# TOP.net
KiCad netlist of a schematic drawn in Altium Designer
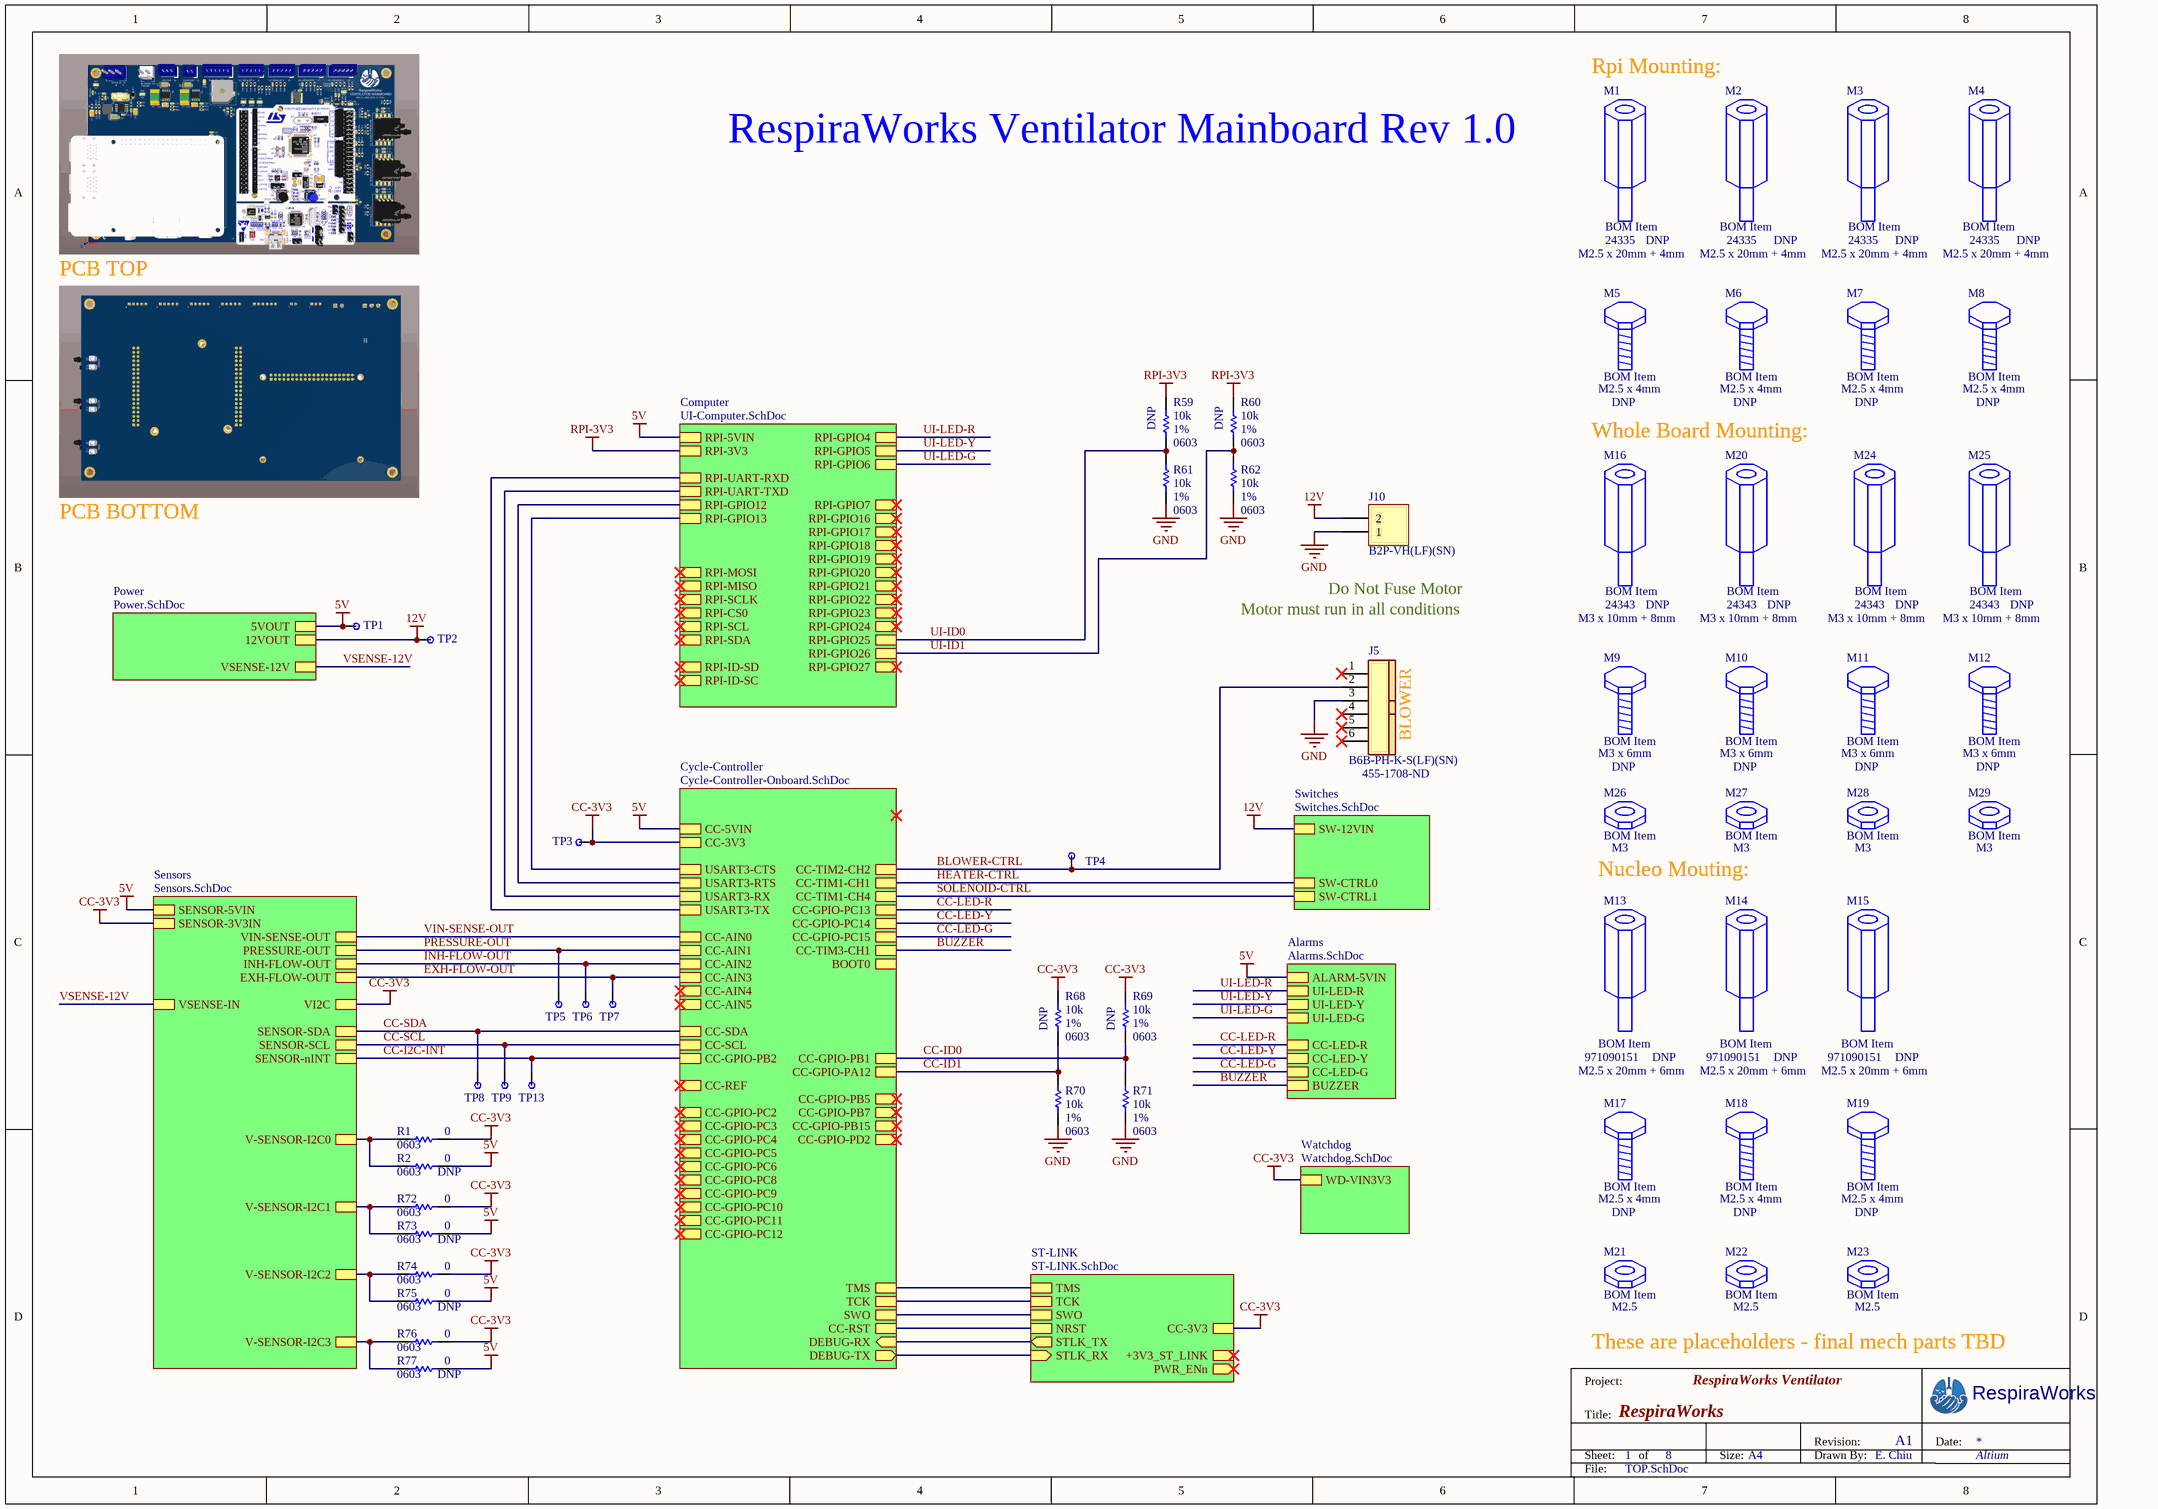
[diagram p0: TOP.SchDoc]

(export (version "E")
  (design (tool "Eeschema 10.0.6"))
  (components
    (comp (ref "J5")
      (value "B6B-PH-K-S(LF)(SN)")
      (footprint "JST_B6B-XH-AM")
      (description "CONN HEADER PH TOP 6POS 2MM")
      (fields
        (field (name "MANUFACTURER") "JST Sales America Inc.")
        (field (name "SUPPLIER PART NUMBER 1") "455-1708-ND")
      )
      (libsource (lib "JST XH") (part "B6B-PH-K-S(LF)(SN)"))
    )
    (comp (ref "J10")
      (value "B2P-VH(LF)(SN)")
      (footprint "B2P-VH(LF)(SN)")
      (description "JST-VH HEADER VERT 2POS 3.96MM")
      (fields (field (name "MANUFACTURER") "JST") (field (name "MANUFACTURER P/N") "B2P-VH(LF)(SN)"))
      (libsource (lib "JST") (part "B2P-VH(LF)(SN)"))
    )
    (comp (ref "M1")
      (value "BOM Item")
      (description "[BOM Item] Generic Standoff")
      (fields
        (field (name "MANUFACTURER") "Keystone")
        (field (name "MANUFACTURER P/N") "24335")
        (field (name "DO NOT POPULATE") "DNP")
        (field (name "ALTIUM_VALUE") "M2.5 x 20mm + 4mm")
      )
      (libsource (lib "generic") (part "STANDOFF"))
    )
    (comp (ref "M2")
      (value "BOM Item")
      (description "[BOM Item] Generic Standoff")
      (fields
        (field (name "MANUFACTURER") "Keystone")
        (field (name "MANUFACTURER P/N") "24335")
        (field (name "DO NOT POPULATE") "DNP")
        (field (name "ALTIUM_VALUE") "M2.5 x 20mm + 4mm")
      )
      (libsource (lib "generic") (part "STANDOFF"))
    )
    (comp (ref "M3")
      (value "BOM Item")
      (description "[BOM Item] Generic Standoff")
      (fields
        (field (name "MANUFACTURER") "Keystone")
        (field (name "MANUFACTURER P/N") "24335")
        (field (name "DO NOT POPULATE") "DNP")
        (field (name "ALTIUM_VALUE") "M2.5 x 20mm + 4mm")
      )
      (libsource (lib "generic") (part "STANDOFF"))
    )
    (comp (ref "M4")
      (value "BOM Item")
      (description "[BOM Item] Generic Standoff")
      (fields
        (field (name "MANUFACTURER") "Keystone")
        (field (name "MANUFACTURER P/N") "24335")
        (field (name "DO NOT POPULATE") "DNP")
        (field (name "ALTIUM_VALUE") "M2.5 x 20mm + 4mm")
      )
      (libsource (lib "generic") (part "STANDOFF"))
    )
    (comp (ref "M5")
      (value "BOM Item")
      (description "[BOM Item] Generic Nut")
      (fields
        (field (name "MANUFACTURER") "Keystone")
        (field (name "DO NOT POPULATE") "DNP")
        (field (name "ALTIUM_VALUE") "M2.5 x 4mm")
      )
      (libsource (lib "generic") (part "SCREW"))
    )
    (comp (ref "M6")
      (value "BOM Item")
      (description "[BOM Item] Generic Nut")
      (fields
        (field (name "MANUFACTURER") "Keystone")
        (field (name "DO NOT POPULATE") "DNP")
        (field (name "ALTIUM_VALUE") "M2.5 x 4mm")
      )
      (libsource (lib "generic") (part "SCREW"))
    )
    (comp (ref "M7")
      (value "BOM Item")
      (description "[BOM Item] Generic Nut")
      (fields
        (field (name "MANUFACTURER") "Keystone")
        (field (name "DO NOT POPULATE") "DNP")
        (field (name "ALTIUM_VALUE") "M2.5 x 4mm")
      )
      (libsource (lib "generic") (part "SCREW"))
    )
    (comp (ref "M8")
      (value "BOM Item")
      (description "[BOM Item] Generic Nut")
      (fields
        (field (name "MANUFACTURER") "Keystone")
        (field (name "DO NOT POPULATE") "DNP")
        (field (name "ALTIUM_VALUE") "M2.5 x 4mm")
      )
      (libsource (lib "generic") (part "SCREW"))
    )
    (comp (ref "M9")
      (value "BOM Item")
      (description "[BOM Item] Generic Nut")
      (fields
        (field (name "MANUFACTURER") "Keystone")
        (field (name "DO NOT POPULATE") "DNP")
        (field (name "ALTIUM_VALUE") "M3 x 6mm")
      )
      (libsource (lib "generic") (part "SCREW"))
    )
    (comp (ref "M10")
      (value "BOM Item")
      (description "[BOM Item] Generic Nut")
      (fields
        (field (name "MANUFACTURER") "Keystone")
        (field (name "DO NOT POPULATE") "DNP")
        (field (name "ALTIUM_VALUE") "M3 x 6mm")
      )
      (libsource (lib "generic") (part "SCREW"))
    )
    (comp (ref "M11")
      (value "BOM Item")
      (description "[BOM Item] Generic Nut")
      (fields
        (field (name "MANUFACTURER") "Keystone")
        (field (name "DO NOT POPULATE") "DNP")
        (field (name "ALTIUM_VALUE") "M3 x 6mm")
      )
      (libsource (lib "generic") (part "SCREW"))
    )
    (comp (ref "M12")
      (value "BOM Item")
      (description "[BOM Item] Generic Nut")
      (fields
        (field (name "MANUFACTURER") "Keystone")
        (field (name "DO NOT POPULATE") "DNP")
        (field (name "ALTIUM_VALUE") "M3 x 6mm")
      )
      (libsource (lib "generic") (part "SCREW"))
    )
    (comp (ref "M13")
      (value "BOM Item")
      (description "[BOM Item] Generic Standoff")
      (fields
        (field (name "MANUFACTURER") "Wurth")
        (field (name "MANUFACTURER P/N") "971090151")
        (field (name "DO NOT POPULATE") "DNP")
        (field (name "ALTIUM_VALUE") "M2.5 x 20mm + 6mm")
      )
      (libsource (lib "generic") (part "STANDOFF"))
    )
    (comp (ref "M14")
      (value "BOM Item")
      (description "[BOM Item] Generic Standoff")
      (fields
        (field (name "MANUFACTURER") "Wurth")
        (field (name "MANUFACTURER P/N") "971090151")
        (field (name "DO NOT POPULATE") "DNP")
        (field (name "ALTIUM_VALUE") "M2.5 x 20mm + 6mm")
      )
      (libsource (lib "generic") (part "STANDOFF"))
    )
    (comp (ref "M15")
      (value "BOM Item")
      (description "[BOM Item] Generic Standoff")
      (fields
        (field (name "MANUFACTURER") "Wurth")
        (field (name "MANUFACTURER P/N") "971090151")
        (field (name "DO NOT POPULATE") "DNP")
        (field (name "ALTIUM_VALUE") "M2.5 x 20mm + 6mm")
      )
      (libsource (lib "generic") (part "STANDOFF"))
    )
    (comp (ref "M16")
      (value "BOM Item")
      (description "[BOM Item] Generic Standoff")
      (fields
        (field (name "MANUFACTURER") "Keystone")
        (field (name "MANUFACTURER P/N") "24343")
        (field (name "DO NOT POPULATE") "DNP")
        (field (name "ALTIUM_VALUE") "M3 x 10mm + 8mm")
      )
      (libsource (lib "generic") (part "STANDOFF"))
    )
    (comp (ref "M17")
      (value "BOM Item")
      (description "[BOM Item] Generic Nut")
      (fields
        (field (name "MANUFACTURER") "Keystone")
        (field (name "DO NOT POPULATE") "DNP")
        (field (name "ALTIUM_VALUE") "M2.5 x 4mm")
      )
      (libsource (lib "generic") (part "SCREW"))
    )
    (comp (ref "M18")
      (value "BOM Item")
      (description "[BOM Item] Generic Nut")
      (fields
        (field (name "MANUFACTURER") "Keystone")
        (field (name "DO NOT POPULATE") "DNP")
        (field (name "ALTIUM_VALUE") "M2.5 x 4mm")
      )
      (libsource (lib "generic") (part "SCREW"))
    )
    (comp (ref "M19")
      (value "BOM Item")
      (description "[BOM Item] Generic Nut")
      (fields
        (field (name "MANUFACTURER") "Keystone")
        (field (name "DO NOT POPULATE") "DNP")
        (field (name "ALTIUM_VALUE") "M2.5 x 4mm")
      )
      (libsource (lib "generic") (part "SCREW"))
    )
    (comp (ref "M20")
      (value "BOM Item")
      (description "[BOM Item] Generic Standoff")
      (fields
        (field (name "MANUFACTURER") "Keystone")
        (field (name "MANUFACTURER P/N") "24343")
        (field (name "DO NOT POPULATE") "DNP")
        (field (name "ALTIUM_VALUE") "M3 x 10mm + 8mm")
      )
      (libsource (lib "generic") (part "STANDOFF"))
    )
    (comp (ref "M21")
      (value "BOM Item")
      (description "[BOM Item] Generic Nut")
      (fields (field (name "MANUFACTURER") "Keystone") (field (name "ALTIUM_VALUE") "M2.5"))
      (libsource (lib "generic") (part "NUT"))
    )
    (comp (ref "M22")
      (value "BOM Item")
      (description "[BOM Item] Generic Nut")
      (fields (field (name "MANUFACTURER") "Keystone") (field (name "ALTIUM_VALUE") "M2.5"))
      (libsource (lib "generic") (part "NUT"))
    )
    (comp (ref "M23")
      (value "BOM Item")
      (description "[BOM Item] Generic Nut")
      (fields (field (name "MANUFACTURER") "Keystone") (field (name "ALTIUM_VALUE") "M2.5"))
      (libsource (lib "generic") (part "NUT"))
    )
    (comp (ref "M24")
      (value "BOM Item")
      (description "[BOM Item] Generic Standoff")
      (fields
        (field (name "MANUFACTURER") "Keystone")
        (field (name "MANUFACTURER P/N") "24343")
        (field (name "DO NOT POPULATE") "DNP")
        (field (name "ALTIUM_VALUE") "M3 x 10mm + 8mm")
      )
      (libsource (lib "generic") (part "STANDOFF"))
    )
    (comp (ref "M25")
      (value "BOM Item")
      (description "[BOM Item] Generic Standoff")
      (fields
        (field (name "MANUFACTURER") "Keystone")
        (field (name "MANUFACTURER P/N") "24343")
        (field (name "DO NOT POPULATE") "DNP")
        (field (name "ALTIUM_VALUE") "M3 x 10mm + 8mm")
      )
      (libsource (lib "generic") (part "STANDOFF"))
    )
    (comp (ref "M26")
      (value "BOM Item")
      (description "[BOM Item] Generic Nut")
      (fields (field (name "MANUFACTURER") "B&F") (field (name "ALTIUM_VALUE") "M3"))
      (libsource (lib "generic") (part "NUT"))
    )
    (comp (ref "M27")
      (value "BOM Item")
      (description "[BOM Item] Generic Nut")
      (fields (field (name "MANUFACTURER") "B&F") (field (name "ALTIUM_VALUE") "M3"))
      (libsource (lib "generic") (part "NUT"))
    )
    (comp (ref "M28")
      (value "BOM Item")
      (description "[BOM Item] Generic Nut")
      (fields (field (name "MANUFACTURER") "B&F") (field (name "ALTIUM_VALUE") "M3"))
      (libsource (lib "generic") (part "NUT"))
    )
    (comp (ref "M29")
      (value "BOM Item")
      (description "[BOM Item] Generic Nut")
      (fields (field (name "MANUFACTURER") "B&F") (field (name "ALTIUM_VALUE") "M3"))
      (libsource (lib "generic") (part "NUT"))
    )
    (comp (ref "R1")
      (value "0")
      (footprint "RES0603")
      (description "Res 0603")
      (fields
        (field (name "MANUFACTURER") "Yageo")
        (field (name "PCB PACKAGE") "0603")
        (field (name "TOLERANCE") "5%")
      )
      (libsource (lib "generic") (part "RES 0603"))
    )
    (comp (ref "R2")
      (value "0")
      (footprint "RES0603")
      (description "Res 0603")
      (fields
        (field (name "MANUFACTURER") "Yageo")
        (field (name "PCB PACKAGE") "0603")
        (field (name "TOLERANCE") "5%")
        (field (name "DO NOT POPULATE") "DNP")
      )
      (libsource (lib "generic") (part "RES 0603"))
    )
    (comp (ref "R59")
      (value "10k")
      (footprint "RES0603")
      (description "Res 0603")
      (fields
        (field (name "MANUFACTURER") "Panasonic")
        (field (name "PCB PACKAGE") "0603")
        (field (name "TOLERANCE") "1%")
        (field (name "DO NOT POPULATE") "DNP")
        (field (name "Comment") "RES 0603")
      )
      (libsource (lib "generic") (part "RES 0603"))
    )
    (comp (ref "R60")
      (value "10k")
      (footprint "RES0603")
      (description "Res 0603")
      (fields
        (field (name "MANUFACTURER") "Panasonic")
        (field (name "PCB PACKAGE") "0603")
        (field (name "TOLERANCE") "1%")
        (field (name "DO NOT POPULATE") "DNP")
        (field (name "Comment") "RES 0603")
      )
      (libsource (lib "generic") (part "RES 0603"))
    )
    (comp (ref "R61")
      (value "10k")
      (footprint "RES0603")
      (description "Res 0603")
      (fields
        (field (name "MANUFACTURER") "Panasonic")
        (field (name "PCB PACKAGE") "0603")
        (field (name "TOLERANCE") "1%")
        (field (name "Comment") "RES 0603")
      )
      (libsource (lib "generic") (part "RES 0603"))
    )
    (comp (ref "R62")
      (value "10k")
      (footprint "RES0603")
      (description "Res 0603")
      (fields
        (field (name "MANUFACTURER") "Panasonic")
        (field (name "PCB PACKAGE") "0603")
        (field (name "TOLERANCE") "1%")
        (field (name "Comment") "RES 0603")
      )
      (libsource (lib "generic") (part "RES 0603"))
    )
    (comp (ref "R68")
      (value "10k")
      (footprint "RES0603")
      (description "Res 0603")
      (fields
        (field (name "MANUFACTURER") "Panasonic")
        (field (name "PCB PACKAGE") "0603")
        (field (name "TOLERANCE") "1%")
        (field (name "DO NOT POPULATE") "DNP")
        (field (name "Comment") "RES 0603")
      )
      (libsource (lib "generic") (part "RES 0603"))
    )
    (comp (ref "R69")
      (value "10k")
      (footprint "RES0603")
      (description "Res 0603")
      (fields
        (field (name "MANUFACTURER") "Panasonic")
        (field (name "PCB PACKAGE") "0603")
        (field (name "TOLERANCE") "1%")
        (field (name "DO NOT POPULATE") "DNP")
        (field (name "Comment") "RES 0603")
      )
      (libsource (lib "generic") (part "RES 0603"))
    )
    (comp (ref "R70")
      (value "10k")
      (footprint "RES0603")
      (description "Res 0603")
      (fields
        (field (name "MANUFACTURER") "Panasonic")
        (field (name "PCB PACKAGE") "0603")
        (field (name "TOLERANCE") "1%")
        (field (name "Comment") "RES 0603")
      )
      (libsource (lib "generic") (part "RES 0603"))
    )
    (comp (ref "R71")
      (value "10k")
      (footprint "RES0603")
      (description "Res 0603")
      (fields
        (field (name "MANUFACTURER") "Panasonic")
        (field (name "PCB PACKAGE") "0603")
        (field (name "TOLERANCE") "1%")
        (field (name "Comment") "RES 0603")
      )
      (libsource (lib "generic") (part "RES 0603"))
    )
    (comp (ref "R72")
      (value "0")
      (footprint "RES0603")
      (description "Res 0603")
      (fields
        (field (name "MANUFACTURER") "Yageo")
        (field (name "PCB PACKAGE") "0603")
        (field (name "TOLERANCE") "5%")
      )
      (libsource (lib "generic") (part "RES 0603"))
    )
    (comp (ref "R73")
      (value "0")
      (footprint "RES0603")
      (description "Res 0603")
      (fields
        (field (name "MANUFACTURER") "Yageo")
        (field (name "PCB PACKAGE") "0603")
        (field (name "TOLERANCE") "5%")
        (field (name "DO NOT POPULATE") "DNP")
      )
      (libsource (lib "generic") (part "RES 0603"))
    )
    (comp (ref "R74")
      (value "0")
      (footprint "RES0603")
      (description "Res 0603")
      (fields
        (field (name "MANUFACTURER") "Yageo")
        (field (name "PCB PACKAGE") "0603")
        (field (name "TOLERANCE") "5%")
      )
      (libsource (lib "generic") (part "RES 0603"))
    )
    (comp (ref "R75")
      (value "0")
      (footprint "RES0603")
      (description "Res 0603")
      (fields
        (field (name "MANUFACTURER") "Yageo")
        (field (name "PCB PACKAGE") "0603")
        (field (name "TOLERANCE") "5%")
        (field (name "DO NOT POPULATE") "DNP")
      )
      (libsource (lib "generic") (part "RES 0603"))
    )
    (comp (ref "R76")
      (value "0")
      (footprint "RES0603")
      (description "Res 0603")
      (fields
        (field (name "MANUFACTURER") "Yageo")
        (field (name "PCB PACKAGE") "0603")
        (field (name "TOLERANCE") "5%")
      )
      (libsource (lib "generic") (part "RES 0603"))
    )
    (comp (ref "R77")
      (value "0")
      (footprint "RES0603")
      (description "Res 0603")
      (fields
        (field (name "MANUFACTURER") "Yageo")
        (field (name "PCB PACKAGE") "0603")
        (field (name "TOLERANCE") "5%")
        (field (name "DO NOT POPULATE") "DNP")
      )
      (libsource (lib "generic") (part "RES 0603"))
    )
    (comp (ref "TP1")
      (value "TP-SMT")
      (footprint "TP-5015")
      (description "Keystone 5015 SMT Mini Testpoint")
      (fields (field (name "MANUFACTURER") "Keystone") (field (name "TOLERANCE") "5015"))
      (libsource (lib "generic") (part "TP-SMT"))
    )
    (comp (ref "TP2")
      (value "TP-SMT")
      (footprint "TP-5015")
      (description "Keystone 5015 SMT Mini Testpoint")
      (fields (field (name "MANUFACTURER") "Keystone") (field (name "TOLERANCE") "5015"))
      (libsource (lib "generic") (part "TP-SMT"))
    )
    (comp (ref "TP3")
      (value "TP-SMT")
      (footprint "TP-5015")
      (description "Keystone 5015 SMT Mini Testpoint")
      (fields (field (name "MANUFACTURER") "Keystone") (field (name "TOLERANCE") "5015"))
      (libsource (lib "generic") (part "TP-SMT"))
    )
    (comp (ref "TP4")
      (value "TP-SMT")
      (footprint "TP-5015")
      (description "Keystone 5015 SMT Mini Testpoint")
      (fields (field (name "MANUFACTURER") "Keystone") (field (name "TOLERANCE") "5015"))
      (libsource (lib "generic") (part "TP-SMT"))
    )
    (comp (ref "TP5")
      (value "TP-SMT")
      (footprint "TP-5015")
      (description "Keystone 5015 SMT Mini Testpoint")
      (fields (field (name "MANUFACTURER") "Keystone") (field (name "TOLERANCE") "5015"))
      (libsource (lib "generic") (part "TP-SMT"))
    )
    (comp (ref "TP6")
      (value "TP-SMT")
      (footprint "TP-5015")
      (description "Keystone 5015 SMT Mini Testpoint")
      (fields (field (name "MANUFACTURER") "Keystone") (field (name "TOLERANCE") "5015"))
      (libsource (lib "generic") (part "TP-SMT"))
    )
    (comp (ref "TP7")
      (value "TP-SMT")
      (footprint "TP-5015")
      (description "Keystone 5015 SMT Mini Testpoint")
      (fields (field (name "MANUFACTURER") "Keystone") (field (name "TOLERANCE") "5015"))
      (libsource (lib "generic") (part "TP-SMT"))
    )
    (comp (ref "TP8")
      (value "TP-SMT")
      (footprint "TP-5015")
      (description "Keystone 5015 SMT Mini Testpoint")
      (fields (field (name "MANUFACTURER") "Keystone") (field (name "TOLERANCE") "5015"))
      (libsource (lib "generic") (part "TP-SMT"))
    )
    (comp (ref "TP9")
      (value "TP-SMT")
      (footprint "TP-5015")
      (description "Keystone 5015 SMT Mini Testpoint")
      (fields (field (name "MANUFACTURER") "Keystone") (field (name "TOLERANCE") "5015"))
      (libsource (lib "generic") (part "TP-SMT"))
    )
    (comp (ref "TP13")
      (value "TP-SMT")
      (footprint "TP-5015")
      (description "Keystone 5015 SMT Mini Testpoint")
      (fields (field (name "MANUFACTURER") "Keystone") (field (name "TOLERANCE") "5015"))
      (libsource (lib "generic") (part "TP-SMT"))
    )
  )
  (nets
    (net (code "2") (name "/BLOWER-CTRL") (class "Default")
      (node (ref "J5") (pin "2") (pinfunction "2_2") (pintype "passive"))
      (node (ref "TP4") (pin "1") (pinfunction "1_1") (pintype "passive"))
    )
    (net (code "21") (name "/CC-I2C-INT") (class "Default")
      (node (ref "TP13") (pin "1") (pinfunction "1_1") (pintype "passive"))
    )
    (net (code "22") (name "/CC-ID0") (class "Default")
      (node (ref "R69") (pin "1") (pinfunction "1_1") (pintype "passive"))
      (node (ref "R71") (pin "2") (pinfunction "2_2") (pintype "passive"))
    )
    (net (code "23") (name "/CC-ID1") (class "Default")
      (node (ref "R68") (pin "1") (pinfunction "1_1") (pintype "passive"))
      (node (ref "R70") (pin "2") (pinfunction "2_2") (pintype "passive"))
    )
    (net (code "29") (name "/CC-SCL") (class "Default")
      (node (ref "TP9") (pin "1") (pinfunction "1_1") (pintype "passive"))
    )
    (net (code "30") (name "/CC-SDA") (class "Default")
      (node (ref "TP8") (pin "1") (pinfunction "1_1") (pintype "passive"))
    )
    (net (code "32") (name "/EXH-FLOW-OUT") (class "Default")
      (node (ref "TP7") (pin "1") (pinfunction "1_1") (pintype "passive"))
    )
    (net (code "34") (name "/INH-FLOW-OUT") (class "Default")
      (node (ref "TP6") (pin "1") (pinfunction "1_1") (pintype "passive"))
    )
    (net (code "35") (name "/PRESSURE-OUT") (class "Default")
      (node (ref "TP5") (pin "1") (pinfunction "1_1") (pintype "passive"))
    )
    (net (code "65") (name "/UI-ID0") (class "Default")
      (node (ref "R59") (pin "1") (pinfunction "1_1") (pintype "passive"))
      (node (ref "R61") (pin "2") (pinfunction "2_2") (pintype "passive"))
    )
    (net (code "66") (name "/UI-ID1") (class "Default")
      (node (ref "R60") (pin "1") (pinfunction "1_1") (pintype "passive"))
      (node (ref "R62") (pin "2") (pinfunction "2_2") (pintype "passive"))
    )
    (net (code "70") (name "/V-SENSOR-I2C0") (class "Default")
      (node (ref "R1") (pin "1") (pinfunction "1_1") (pintype "passive"))
      (node (ref "R2") (pin "1") (pinfunction "1_1") (pintype "passive"))
    )
    (net (code "71") (name "/V-SENSOR-I2C1") (class "Default")
      (node (ref "R72") (pin "1") (pinfunction "1_1") (pintype "passive"))
      (node (ref "R73") (pin "1") (pinfunction "1_1") (pintype "passive"))
    )
    (net (code "72") (name "/V-SENSOR-I2C2") (class "Default")
      (node (ref "R74") (pin "1") (pinfunction "1_1") (pintype "passive"))
      (node (ref "R75") (pin "1") (pinfunction "1_1") (pintype "passive"))
    )
    (net (code "73") (name "/V-SENSOR-I2C3") (class "Default")
      (node (ref "R76") (pin "1") (pinfunction "1_1") (pintype "passive"))
      (node (ref "R77") (pin "1") (pinfunction "1_1") (pintype "passive"))
    )
    (net (code "76") (name "5V") (class "Default")
      (node (ref "R2") (pin "2") (pinfunction "2_2") (pintype "passive"))
      (node (ref "R73") (pin "2") (pinfunction "2_2") (pintype "passive"))
      (node (ref "R75") (pin "2") (pinfunction "2_2") (pintype "passive"))
      (node (ref "R77") (pin "2") (pinfunction "2_2") (pintype "passive"))
      (node (ref "TP1") (pin "1") (pinfunction "1_1") (pintype "passive"))
    )
    (net (code "77") (name "12V") (class "Default")
      (node (ref "J10") (pin "2") (pinfunction "2_2") (pintype "passive"))
      (node (ref "TP2") (pin "1") (pinfunction "1_1") (pintype "passive"))
    )
    (net (code "78") (name "CC-3V3") (class "Default")
      (node (ref "R1") (pin "2") (pinfunction "2_2") (pintype "passive"))
      (node (ref "R68") (pin "2") (pinfunction "2_2") (pintype "passive"))
      (node (ref "R69") (pin "2") (pinfunction "2_2") (pintype "passive"))
      (node (ref "R72") (pin "2") (pinfunction "2_2") (pintype "passive"))
      (node (ref "R74") (pin "2") (pinfunction "2_2") (pintype "passive"))
      (node (ref "R76") (pin "2") (pinfunction "2_2") (pintype "passive"))
      (node (ref "TP3") (pin "1") (pinfunction "1_1") (pintype "passive"))
    )
    (net (code "79") (name "GND") (class "Default")
      (node (ref "J10") (pin "1") (pinfunction "1_1") (pintype "passive"))
      (node (ref "J5") (pin "3") (pinfunction "3_3") (pintype "passive"))
      (node (ref "R61") (pin "1") (pinfunction "1_1") (pintype "passive"))
      (node (ref "R62") (pin "1") (pinfunction "1_1") (pintype "passive"))
      (node (ref "R70") (pin "1") (pinfunction "1_1") (pintype "passive"))
      (node (ref "R71") (pin "1") (pinfunction "1_1") (pintype "passive"))
    )
    (net (code "80") (name "RPI-3V3") (class "Default")
      (node (ref "R59") (pin "2") (pinfunction "2_2") (pintype "passive"))
      (node (ref "R60") (pin "2") (pinfunction "2_2") (pintype "passive"))
    )
    (net (code "81") (name "unconnected-(J5-Pad1)") (class "Default")
      (node (ref "J5") (pin "1") (pinfunction "1_1") (pintype "passive+no_connect"))
    )
    (net (code "82") (name "unconnected-(J5-Pad4)") (class "Default")
      (node (ref "J5") (pin "4") (pinfunction "4_4") (pintype "passive+no_connect"))
    )
    (net (code "83") (name "unconnected-(J5-Pad5)") (class "Default")
      (node (ref "J5") (pin "5") (pinfunction "5_5") (pintype "passive+no_connect"))
    )
    (net (code "84") (name "unconnected-(J5-Pad6)") (class "Default")
      (node (ref "J5") (pin "6") (pinfunction "6_6") (pintype "passive+no_connect"))
    )
  )
)
